# ledtiny85.net
KiCad netlist of a schematic drawn in EAGLE
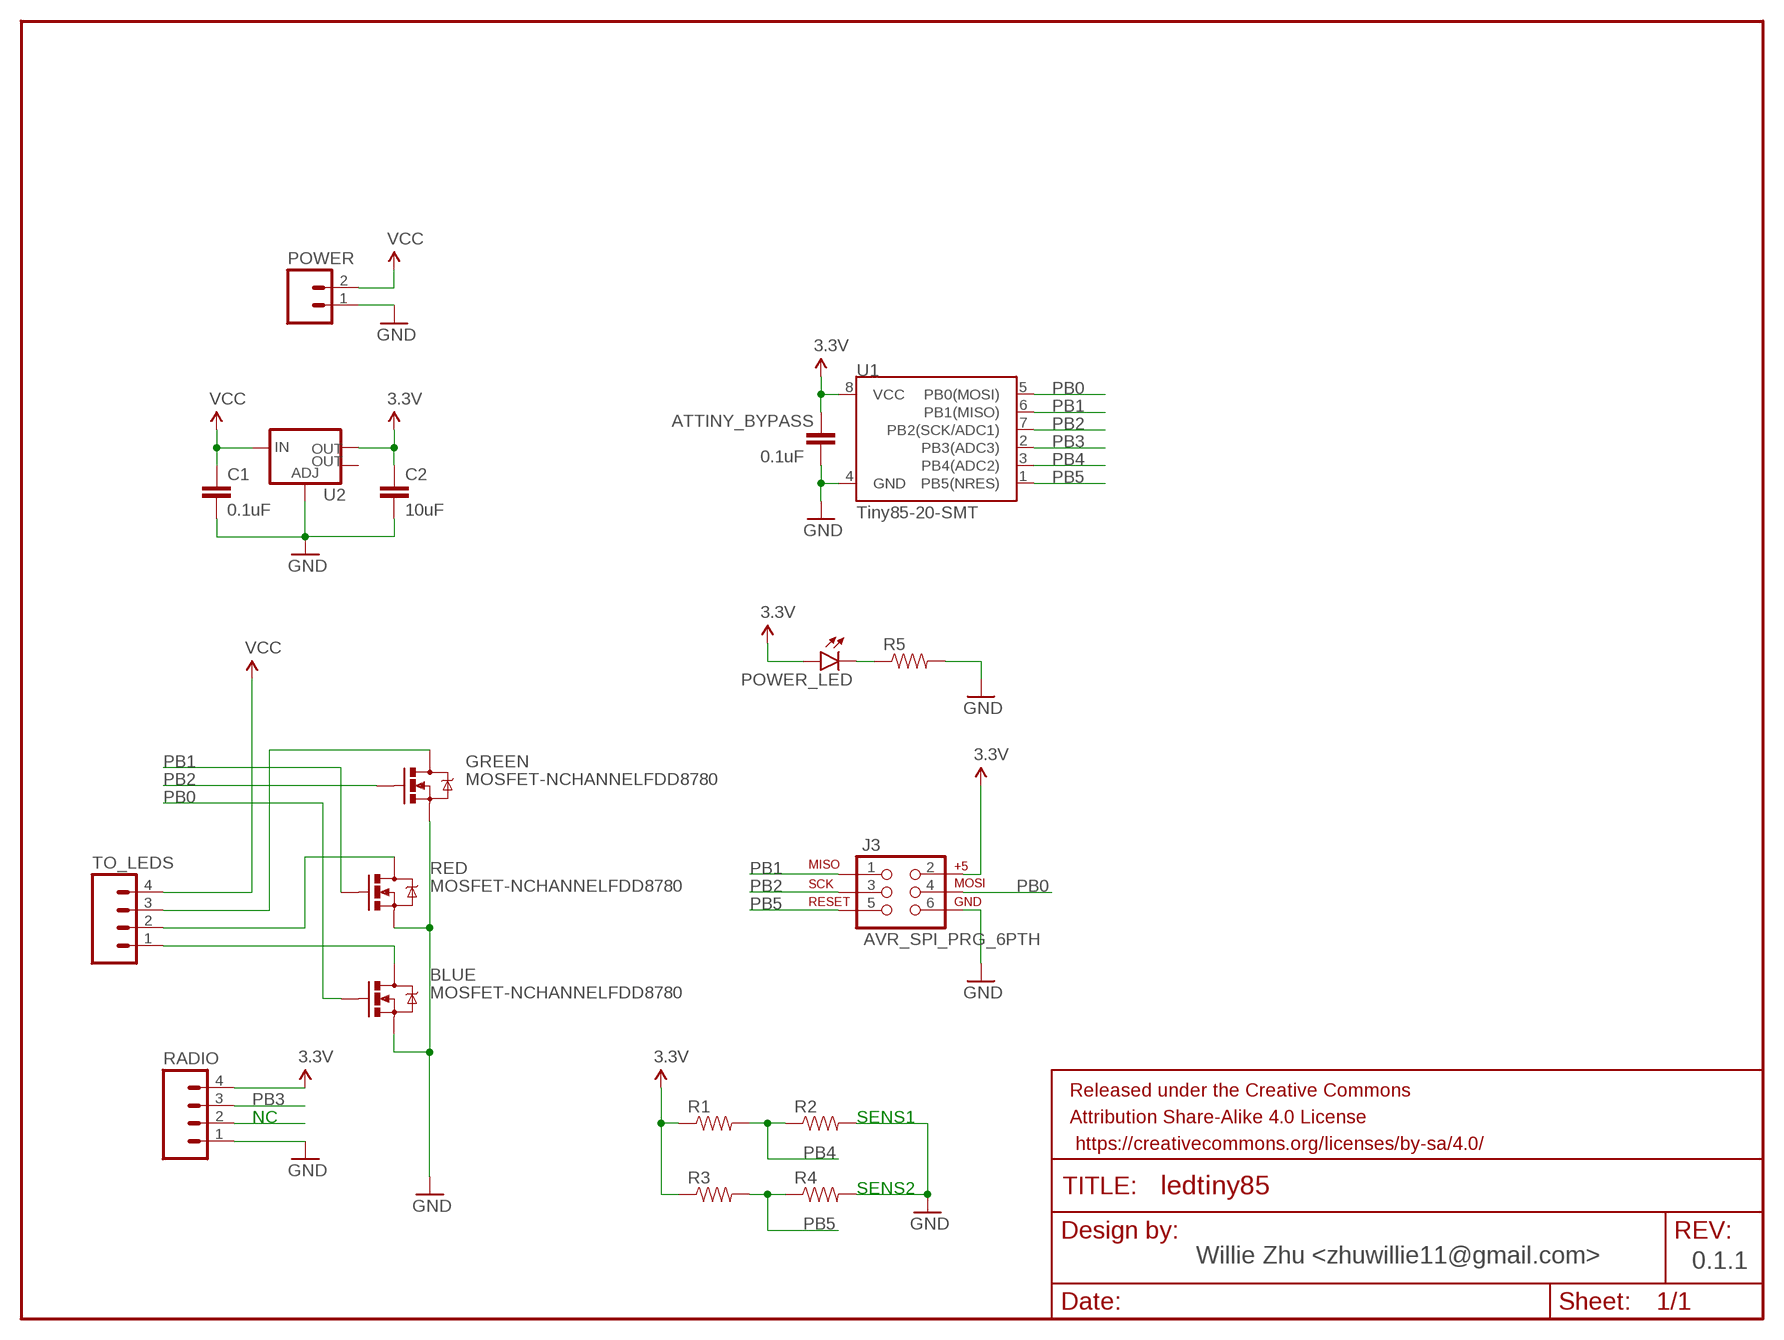
[diagram p0: schematic, sheet 1]

(export (version "E")
  (design (tool "Eeschema 10.0.6"))
  (components
    (comp (ref "ATTINY_BYPASS")
      (value "0.1uF")
      (footprint "eagle-import:1206")
      (libsource (lib "eagle-import") (part "CAP1206"))
    )
    (comp (ref "BLUE")
      (value "MOSFET-NCHANNELFDD8780")
      (footprint "eagle-import:DPAK")
      (libsource (lib "eagle-import") (part "MOSFET-NCHANNELFDD8780"))
    )
    (comp (ref "C1")
      (value "0.1uF")
      (footprint "eagle-import:1206")
      (libsource (lib "eagle-import") (part "CAP1206"))
    )
    (comp (ref "C2")
      (value "10uF")
      (footprint "eagle-import:1206")
      (libsource (lib "eagle-import") (part "CAP1206"))
    )
    (comp (ref "FRAME1")
      (value "FRAME-LETTER")
      (footprint "eagle-import:CREATIVE_COMMONS")
      (libsource (lib "eagle-import") (part "FRAME-LETTER"))
    )
    (comp (ref "GREEN")
      (value "MOSFET-NCHANNELFDD8780")
      (footprint "eagle-import:DPAK")
      (libsource (lib "eagle-import") (part "MOSFET-NCHANNELFDD8780"))
    )
    (comp (ref "J3")
      (value "AVR_SPI_PRG_6PTH")
      (footprint "eagle-import:2X3")
      (libsource (lib "eagle-import") (part "AVR_SPI_PRG_6PTH"))
    )
    (comp (ref "POWER")
      (value "M02PTH3")
      (footprint "eagle-import:1X02_LONGPADS")
      (libsource (lib "eagle-import") (part "M02PTH3"))
    )
    (comp (ref "POWER_LED")
      (value "LED1206")
      (footprint "eagle-import:LED-1206")
      (libsource (lib "eagle-import") (part "LED1206"))
    )
    (comp (ref "R1")
      (value "RESISTOR1206")
      (footprint "eagle-import:1206")
      (libsource (lib "eagle-import") (part "RESISTOR1206"))
    )
    (comp (ref "R2")
      (value "RESISTOR1206")
      (footprint "eagle-import:1206")
      (libsource (lib "eagle-import") (part "RESISTOR1206"))
    )
    (comp (ref "R3")
      (value "RESISTOR1206")
      (footprint "eagle-import:1206")
      (libsource (lib "eagle-import") (part "RESISTOR1206"))
    )
    (comp (ref "R4")
      (value "RESISTOR1206")
      (footprint "eagle-import:1206")
      (libsource (lib "eagle-import") (part "RESISTOR1206"))
    )
    (comp (ref "R5")
      (value "RESISTOR1206")
      (footprint "eagle-import:1206")
      (libsource (lib "eagle-import") (part "RESISTOR1206"))
    )
    (comp (ref "RADIO")
      (value "M04LONGPADS")
      (footprint "eagle-import:1X04_LONGPADS")
      (libsource (lib "eagle-import") (part "M04LONGPADS"))
    )
    (comp (ref "RED")
      (value "MOSFET-NCHANNELFDD8780")
      (footprint "eagle-import:DPAK")
      (libsource (lib "eagle-import") (part "MOSFET-NCHANNELFDD8780"))
    )
    (comp (ref "TO_LEDS")
      (value "M04LONGPADS")
      (footprint "eagle-import:1X04_LONGPADS")
      (libsource (lib "eagle-import") (part "M04LONGPADS"))
    )
    (comp (ref "U1")
      (value "Tiny85-20-SMT")
      (footprint "eagle-import:SO08-EIAJ")
      (libsource (lib "eagle-import") (part "ATTINY45TINY85-20-SMT"))
    )
    (comp (ref "U2")
      (value "V_REG_LM1117SOT223")
      (footprint "eagle-import:SOT223")
      (libsource (lib "eagle-import") (part "V_REG_LM1117SOT223"))
    )
  )
  (nets
    (net (code "1") (name "/PB0") (class "Default")
      (node (ref "BLUE") (pin "1") (pinfunction "G_1") (pintype "passive"))
      (node (ref "J3") (pin "4") (pinfunction "4_4") (pintype "passive"))
      (node (ref "U1") (pin "5") (pinfunction "PB0(MOSI)_5") (pintype "bidirectional"))
    )
    (net (code "2") (name "/PB1") (class "Default")
      (node (ref "J3") (pin "1") (pinfunction "1_1") (pintype "passive"))
      (node (ref "RED") (pin "1") (pinfunction "G_1") (pintype "passive"))
      (node (ref "U1") (pin "6") (pinfunction "PB1(MISO)_6") (pintype "bidirectional"))
    )
    (net (code "3") (name "/PB2") (class "Default")
      (node (ref "GREEN") (pin "1") (pinfunction "G_1") (pintype "passive"))
      (node (ref "J3") (pin "3") (pinfunction "3_3") (pintype "passive"))
      (node (ref "U1") (pin "7") (pinfunction "PB2(SCK/ADC1)_7") (pintype "bidirectional"))
    )
    (net (code "4") (name "/PB3") (class "Default")
      (node (ref "RADIO") (pin "3") (pinfunction "3_3") (pintype "passive"))
      (node (ref "U1") (pin "2") (pinfunction "PB3(ADC3)_2") (pintype "bidirectional"))
    )
    (net (code "5") (name "/PB4") (class "Default")
      (node (ref "R1") (pin "2") (pinfunction "2_2") (pintype "passive"))
      (node (ref "R2") (pin "1") (pinfunction "1_1") (pintype "passive"))
      (node (ref "U1") (pin "3") (pinfunction "PB4(ADC2)_3") (pintype "bidirectional"))
    )
    (net (code "6") (name "/PB5") (class "Default")
      (node (ref "J3") (pin "5") (pinfunction "5_5") (pintype "passive"))
      (node (ref "R3") (pin "2") (pinfunction "2_2") (pintype "passive"))
      (node (ref "R4") (pin "1") (pinfunction "1_1") (pintype "passive"))
      (node (ref "U1") (pin "1") (pinfunction "PB5(NRES)_1") (pintype "bidirectional"))
    )
    (net (code "7") (name "3.3V") (class "Default")
      (node (ref "ATTINY_BYPASS") (pin "1") (pinfunction "1_1") (pintype "passive"))
      (node (ref "C2") (pin "1") (pinfunction "1_1") (pintype "passive"))
      (node (ref "J3") (pin "2") (pinfunction "2_2") (pintype "passive"))
      (node (ref "POWER_LED") (pin "A") (pinfunction "A_A") (pintype "passive"))
      (node (ref "R1") (pin "1") (pinfunction "1_1") (pintype "passive"))
      (node (ref "R3") (pin "1") (pinfunction "1_1") (pintype "passive"))
      (node (ref "RADIO") (pin "4") (pinfunction "4_4") (pintype "passive"))
      (node (ref "U1") (pin "8") (pinfunction "VCC_8") (pintype "bidirectional"))
      (node (ref "U2") (pin "2") (pinfunction "OUT_2") (pintype "output"))
    )
    (net (code "8") (name "GND") (class "Default")
      (node (ref "ATTINY_BYPASS") (pin "2") (pinfunction "2_2") (pintype "passive"))
      (node (ref "BLUE") (pin "3") (pinfunction "S_3") (pintype "passive"))
      (node (ref "C1") (pin "2") (pinfunction "2_2") (pintype "passive"))
      (node (ref "C2") (pin "2") (pinfunction "2_2") (pintype "passive"))
      (node (ref "GREEN") (pin "3") (pinfunction "S_3") (pintype "passive"))
      (node (ref "J3") (pin "6") (pinfunction "6_6") (pintype "passive"))
      (node (ref "POWER") (pin "1") (pinfunction "1_1") (pintype "passive"))
      (node (ref "R2") (pin "2") (pinfunction "2_2") (pintype "passive"))
      (node (ref "R4") (pin "2") (pinfunction "2_2") (pintype "passive"))
      (node (ref "R5") (pin "2") (pinfunction "2_2") (pintype "passive"))
      (node (ref "RADIO") (pin "1") (pinfunction "1_1") (pintype "passive"))
      (node (ref "RED") (pin "3") (pinfunction "S_3") (pintype "passive"))
      (node (ref "U1") (pin "4") (pinfunction "GND_4") (pintype "bidirectional"))
      (node (ref "U2") (pin "1") (pinfunction "ADJ_1") (pintype "input"))
    )
    (net (code "9") (name "Net-(BLUE-D)") (class "Default")
      (node (ref "BLUE") (pin "4") (pinfunction "D_4") (pintype "passive"))
      (node (ref "TO_LEDS") (pin "1") (pinfunction "1_1") (pintype "passive"))
    )
    (net (code "10") (name "Net-(GREEN-D)") (class "Default")
      (node (ref "GREEN") (pin "4") (pinfunction "D_4") (pintype "passive"))
      (node (ref "TO_LEDS") (pin "3") (pinfunction "3_3") (pintype "passive"))
    )
    (net (code "11") (name "Net-(POWER_LED-PadC)") (class "Default")
      (node (ref "POWER_LED") (pin "C") (pinfunction "C_C") (pintype "passive"))
      (node (ref "R5") (pin "1") (pinfunction "1_1") (pintype "passive"))
    )
    (net (code "12") (name "Net-(RED-D)") (class "Default")
      (node (ref "RED") (pin "4") (pinfunction "D_4") (pintype "passive"))
      (node (ref "TO_LEDS") (pin "2") (pinfunction "2_2") (pintype "passive"))
    )
    (net (code "13") (name "VCC") (class "Default")
      (node (ref "C1") (pin "1") (pinfunction "1_1") (pintype "passive"))
      (node (ref "POWER") (pin "2") (pinfunction "2_2") (pintype "passive"))
      (node (ref "TO_LEDS") (pin "4") (pinfunction "4_4") (pintype "passive"))
      (node (ref "U2") (pin "3") (pinfunction "IN_3") (pintype "input"))
    )
    (net (code "14") (name "unconnected-(RADIO-Pad2)") (class "Default")
      (node (ref "RADIO") (pin "2") (pinfunction "2_2") (pintype "passive"))
    )
    (net (code "15") (name "unconnected-(U2-OUT-Pad4)") (class "Default")
      (node (ref "U2") (pin "4") (pinfunction "OUT_4") (pintype "output"))
    )
  )
)
